# nRF-Serial-v12-Class-vrs.net
KiCad netlist of a schematic drawn in EAGLE
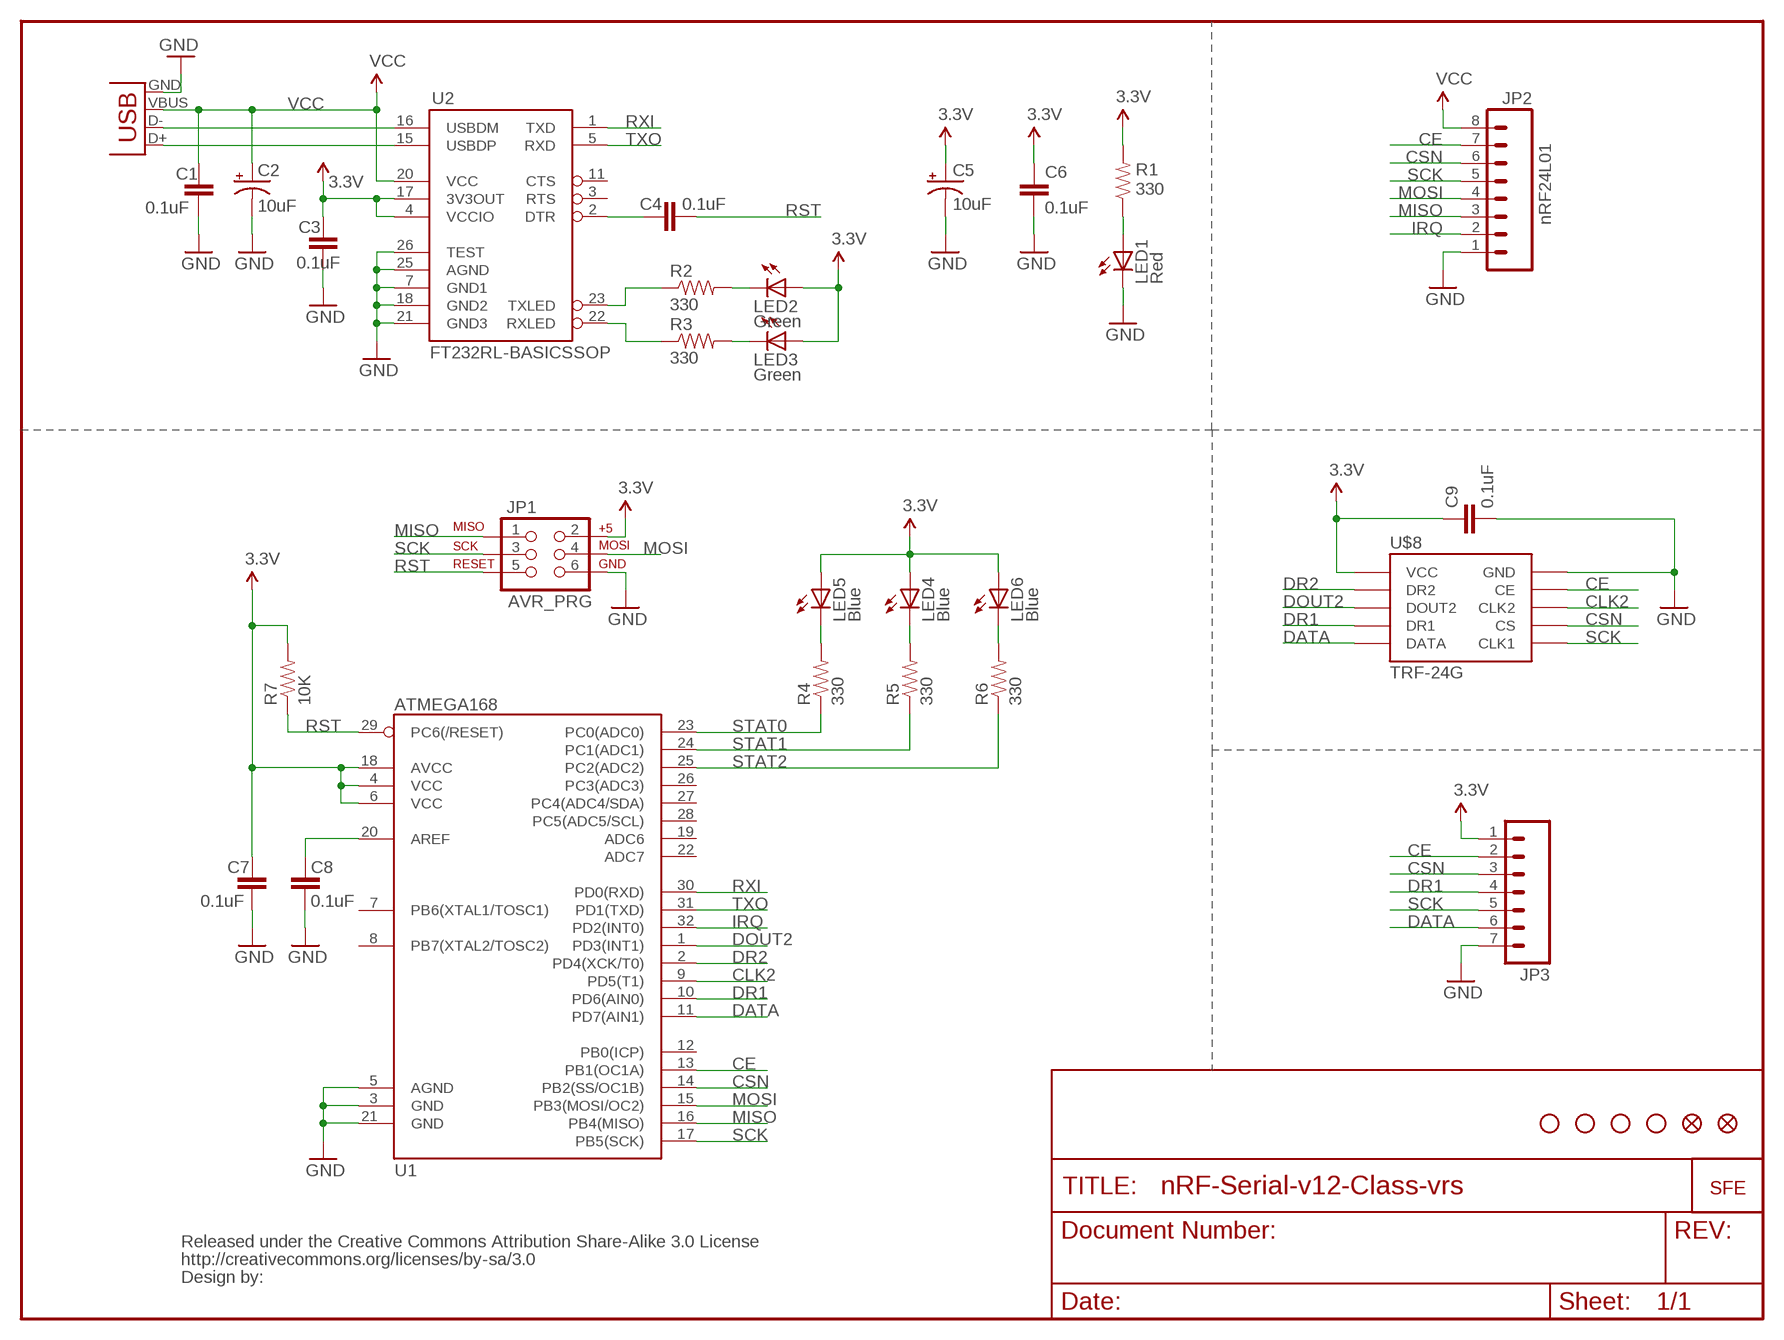
[diagram p0: schematic, sheet 1]

(export (version "E")
  (design (tool "Eeschema 10.0.6"))
  (components
    (comp (ref "C1")
      (value "0.1uF")
      (footprint "eagle-import:C0402")
      (libsource (lib "eagle-import") (part "CAP0402"))
    )
    (comp (ref "C2")
      (value "10uF")
      (footprint "eagle-import:EIA3216")
      (libsource (lib "eagle-import") (part "CAP_POL1206"))
    )
    (comp (ref "C3")
      (value "0.1uF")
      (footprint "eagle-import:C0402")
      (libsource (lib "eagle-import") (part "CAP0402"))
    )
    (comp (ref "C4")
      (value "0.1uF")
      (footprint "eagle-import:C0402")
      (libsource (lib "eagle-import") (part "CAP0402"))
    )
    (comp (ref "C5")
      (value "10uF")
      (footprint "eagle-import:EIA3216")
      (libsource (lib "eagle-import") (part "CAP_POL1206"))
    )
    (comp (ref "C6")
      (value "0.1uF")
      (footprint "eagle-import:C0402")
      (libsource (lib "eagle-import") (part "CAP0402"))
    )
    (comp (ref "C7")
      (value "0.1uF")
      (footprint "eagle-import:C0402")
      (libsource (lib "eagle-import") (part "CAP0402"))
    )
    (comp (ref "C8")
      (value "0.1uF")
      (footprint "eagle-import:C0402")
      (libsource (lib "eagle-import") (part "CAP0402"))
    )
    (comp (ref "C9")
      (value "0.1uF")
      (footprint "eagle-import:C0402")
      (libsource (lib "eagle-import") (part "CAP0402"))
    )
    (comp (ref "JP1")
      (value "AVR_PRG")
      (footprint "eagle-import:2X3")
      (libsource (lib "eagle-import") (part "AVR_SPI_PRG_6PTH"))
    )
    (comp (ref "JP2")
      (value "nRF24L01")
      (footprint "eagle-import:1X08")
      (libsource (lib "eagle-import") (part "M08"))
    )
    (comp (ref "JP3")
      (value "M07")
      (footprint "eagle-import:1X07")
      (libsource (lib "eagle-import") (part "M07"))
    )
    (comp (ref "LED1")
      (value "Red")
      (footprint "eagle-import:LED-0603")
      (libsource (lib "eagle-import") (part "LED0603"))
    )
    (comp (ref "LED2")
      (value "Green")
      (footprint "eagle-import:LED-0603")
      (libsource (lib "eagle-import") (part "LED0603"))
    )
    (comp (ref "LED3")
      (value "Green")
      (footprint "eagle-import:LED-0603")
      (libsource (lib "eagle-import") (part "LED0603"))
    )
    (comp (ref "LED4")
      (value "Blue")
      (footprint "eagle-import:LED-0603")
      (libsource (lib "eagle-import") (part "LED0603"))
    )
    (comp (ref "LED5")
      (value "Blue")
      (footprint "eagle-import:LED-0603")
      (libsource (lib "eagle-import") (part "LED0603"))
    )
    (comp (ref "LED6")
      (value "Blue")
      (footprint "eagle-import:LED-0603")
      (libsource (lib "eagle-import") (part "LED0603"))
    )
    (comp (ref "R1")
      (value "330")
      (footprint "eagle-import:C0402")
      (libsource (lib "eagle-import") (part "RESISTOR0402"))
    )
    (comp (ref "R2")
      (value "330")
      (footprint "eagle-import:C0402")
      (libsource (lib "eagle-import") (part "RESISTOR0402"))
    )
    (comp (ref "R3")
      (value "330")
      (footprint "eagle-import:C0402")
      (libsource (lib "eagle-import") (part "RESISTOR0402"))
    )
    (comp (ref "R4")
      (value "330")
      (footprint "eagle-import:C0402")
      (libsource (lib "eagle-import") (part "RESISTOR0402"))
    )
    (comp (ref "R5")
      (value "330")
      (footprint "eagle-import:C0402")
      (libsource (lib "eagle-import") (part "RESISTOR0402"))
    )
    (comp (ref "R6")
      (value "330")
      (footprint "eagle-import:C0402")
      (libsource (lib "eagle-import") (part "RESISTOR0402"))
    )
    (comp (ref "R7")
      (value "10K")
      (footprint "eagle-import:C0402")
      (libsource (lib "eagle-import") (part "RESISTOR0402"))
    )
    (comp (ref "U$1")
      (value "LOGO-SFENEW")
      (footprint "eagle-import:SFE-NEW-WEBLOGO")
      (libsource (lib "eagle-import") (part "LOGO-SFENEW"))
    )
    (comp (ref "U$2")
      (value "FIDUCIAL1X2")
      (footprint "eagle-import:FIDUCIAL-1X2")
      (libsource (lib "eagle-import") (part "FIDUCIAL1X2"))
    )
    (comp (ref "U$3")
      (value "FIDUCIAL1X2")
      (footprint "eagle-import:FIDUCIAL-1X2")
      (libsource (lib "eagle-import") (part "FIDUCIAL1X2"))
    )
    (comp (ref "U$4")
      (value "STAND-OFF")
      (footprint "eagle-import:STAND-OFF")
      (libsource (lib "eagle-import") (part "STAND-OFF"))
    )
    (comp (ref "U$5")
      (value "STAND-OFF")
      (footprint "eagle-import:STAND-OFF")
      (libsource (lib "eagle-import") (part "STAND-OFF"))
    )
    (comp (ref "U$6")
      (value "STAND-OFF")
      (footprint "eagle-import:STAND-OFF")
      (libsource (lib "eagle-import") (part "STAND-OFF"))
    )
    (comp (ref "U$7")
      (value "STAND-OFF")
      (footprint "eagle-import:STAND-OFF")
      (libsource (lib "eagle-import") (part "STAND-OFF"))
    )
    (comp (ref "U$8")
      (value "TRF-24G")
      (footprint "eagle-import:TRF-24G-SOCKET")
      (libsource (lib "eagle-import") (part "TRF-24G"))
    )
    (comp (ref "U$9")
      (value "CREATIVE_COMMONS")
      (footprint "eagle-import:CREATIVE_COMMONS")
      (libsource (lib "eagle-import") (part "CREATIVE_COMMONS"))
    )
    (comp (ref "U1")
      (value "ATMEGA168")
      (footprint "eagle-import:TQFP32-08")
      (libsource (lib "eagle-import") (part "ATMEGA168"))
    )
    (comp (ref "U2")
      (value "FT232RL-BASICSSOP")
      (footprint "eagle-import:SSOP28DB")
      (libsource (lib "eagle-import") (part "FT232RL-BASICSSOP"))
    )
    (comp (ref "X1")
      (value "USBSMD")
      (footprint "eagle-import:USB-MINIB")
      (libsource (lib "eagle-import") (part "USBSMD"))
    )
  )
  (nets
    (net (code "1") (name "/CE") (class "Default")
      (node (ref "JP2") (pin "7") (pinfunction "7_7") (pintype "passive"))
      (node (ref "JP3") (pin "2") (pinfunction "2_2") (pintype "passive"))
      (node (ref "U$8") (pin "P$9") (pinfunction "CE_P$9") (pintype "bidirectional"))
      (node (ref "U1") (pin "13") (pinfunction "PB1(OC1A)_13") (pintype "bidirectional"))
    )
    (net (code "2") (name "/CLK2") (class "Default")
      (node (ref "U$8") (pin "P$8") (pinfunction "CLK2_P$8") (pintype "bidirectional"))
      (node (ref "U1") (pin "9") (pinfunction "PD5(T1)_9") (pintype "bidirectional"))
    )
    (net (code "3") (name "/CSN") (class "Default")
      (node (ref "JP2") (pin "6") (pinfunction "6_6") (pintype "passive"))
      (node (ref "JP3") (pin "3") (pinfunction "3_3") (pintype "passive"))
      (node (ref "U$8") (pin "P$7") (pinfunction "CS_P$7") (pintype "bidirectional"))
      (node (ref "U1") (pin "14") (pinfunction "PB2(SS/OC1B)_14") (pintype "bidirectional"))
    )
    (net (code "4") (name "/DATA") (class "Default")
      (node (ref "JP3") (pin "6") (pinfunction "6_6") (pintype "passive"))
      (node (ref "U$8") (pin "P$5") (pinfunction "DATA_P$5") (pintype "bidirectional"))
      (node (ref "U1") (pin "11") (pinfunction "PD7(AIN1)_11") (pintype "bidirectional"))
    )
    (net (code "5") (name "/DOUT2") (class "Default")
      (node (ref "U$8") (pin "P$3") (pinfunction "DOUT2_P$3") (pintype "bidirectional"))
      (node (ref "U1") (pin "1") (pinfunction "PD3(INT1)_1") (pintype "bidirectional"))
    )
    (net (code "6") (name "/DR1") (class "Default")
      (node (ref "JP3") (pin "4") (pinfunction "4_4") (pintype "passive"))
      (node (ref "U$8") (pin "P$4") (pinfunction "DR1_P$4") (pintype "bidirectional"))
      (node (ref "U1") (pin "10") (pinfunction "PD6(AIN0)_10") (pintype "bidirectional"))
    )
    (net (code "7") (name "/DR2") (class "Default")
      (node (ref "U$8") (pin "P$2") (pinfunction "DR2_P$2") (pintype "bidirectional"))
      (node (ref "U1") (pin "2") (pinfunction "PD4(XCK/T0)_2") (pintype "bidirectional"))
    )
    (net (code "8") (name "/IRQ") (class "Default")
      (node (ref "JP2") (pin "2") (pinfunction "2_2") (pintype "passive"))
      (node (ref "U1") (pin "32") (pinfunction "PD2(INT0)_32") (pintype "bidirectional"))
    )
    (net (code "9") (name "/MISO") (class "Default")
      (node (ref "JP1") (pin "1") (pinfunction "1_1") (pintype "passive"))
      (node (ref "JP2") (pin "3") (pinfunction "3_3") (pintype "passive"))
      (node (ref "U1") (pin "16") (pinfunction "PB4(MISO)_16") (pintype "bidirectional"))
    )
    (net (code "10") (name "/MOSI") (class "Default")
      (node (ref "JP1") (pin "4") (pinfunction "4_4") (pintype "passive"))
      (node (ref "JP2") (pin "4") (pinfunction "4_4") (pintype "passive"))
      (node (ref "U1") (pin "15") (pinfunction "PB3(MOSI/OC2)_15") (pintype "bidirectional"))
    )
    (net (code "11") (name "/RST") (class "Default")
      (node (ref "C4") (pin "1") (pinfunction "1_1") (pintype "passive"))
      (node (ref "JP1") (pin "5") (pinfunction "5_5") (pintype "passive"))
      (node (ref "R7") (pin "1") (pinfunction "1_1") (pintype "passive"))
      (node (ref "U1") (pin "29") (pinfunction "PC6(/RESET)_29") (pintype "bidirectional"))
    )
    (net (code "12") (name "/RXI") (class "Default")
      (node (ref "U1") (pin "30") (pinfunction "PD0(RXD)_30") (pintype "bidirectional"))
      (node (ref "U2") (pin "1") (pinfunction "TXD_1") (pintype "output"))
    )
    (net (code "13") (name "/SCK") (class "Default")
      (node (ref "JP1") (pin "3") (pinfunction "3_3") (pintype "passive"))
      (node (ref "JP2") (pin "5") (pinfunction "5_5") (pintype "passive"))
      (node (ref "JP3") (pin "5") (pinfunction "5_5") (pintype "passive"))
      (node (ref "U$8") (pin "P$6") (pinfunction "CLK1_P$6") (pintype "bidirectional"))
      (node (ref "U1") (pin "17") (pinfunction "PB5(SCK)_17") (pintype "bidirectional"))
    )
    (net (code "14") (name "/STAT0") (class "Default")
      (node (ref "R4") (pin "1") (pinfunction "1_1") (pintype "passive"))
      (node (ref "U1") (pin "23") (pinfunction "PC0(ADC0)_23") (pintype "bidirectional"))
    )
    (net (code "15") (name "/STAT1") (class "Default")
      (node (ref "R5") (pin "1") (pinfunction "1_1") (pintype "passive"))
      (node (ref "U1") (pin "24") (pinfunction "PC1(ADC1)_24") (pintype "bidirectional"))
    )
    (net (code "16") (name "/STAT2") (class "Default")
      (node (ref "R6") (pin "1") (pinfunction "1_1") (pintype "passive"))
      (node (ref "U1") (pin "25") (pinfunction "PC2(ADC2)_25") (pintype "bidirectional"))
    )
    (net (code "17") (name "/TXO") (class "Default")
      (node (ref "U1") (pin "31") (pinfunction "PD1(TXD)_31") (pintype "bidirectional"))
      (node (ref "U2") (pin "5") (pinfunction "RXD_5") (pintype "input"))
    )
    (net (code "18") (name "3.3V") (class "Default")
      (node (ref "C3") (pin "1") (pinfunction "1_1") (pintype "passive"))
      (node (ref "C5") (pin "A") (pinfunction "+_A") (pintype "passive"))
      (node (ref "C6") (pin "1") (pinfunction "1_1") (pintype "passive"))
      (node (ref "C7") (pin "1") (pinfunction "1_1") (pintype "passive"))
      (node (ref "C9") (pin "1") (pinfunction "1_1") (pintype "passive"))
      (node (ref "JP1") (pin "2") (pinfunction "2_2") (pintype "passive"))
      (node (ref "JP3") (pin "1") (pinfunction "1_1") (pintype "passive"))
      (node (ref "LED2") (pin "A") (pinfunction "A_A") (pintype "passive"))
      (node (ref "LED3") (pin "A") (pinfunction "A_A") (pintype "passive"))
      (node (ref "LED4") (pin "A") (pinfunction "A_A") (pintype "passive"))
      (node (ref "LED5") (pin "A") (pinfunction "A_A") (pintype "passive"))
      (node (ref "LED6") (pin "A") (pinfunction "A_A") (pintype "passive"))
      (node (ref "R1") (pin "2") (pinfunction "2_2") (pintype "passive"))
      (node (ref "R7") (pin "2") (pinfunction "2_2") (pintype "passive"))
      (node (ref "U$8") (pin "P$1") (pinfunction "VCC_P$1") (pintype "bidirectional"))
      (node (ref "U1") (pin "18") (pinfunction "AVCC_18") (pintype "bidirectional"))
      (node (ref "U1") (pin "4") (pinfunction "VCC_4") (pintype "bidirectional"))
      (node (ref "U1") (pin "6") (pinfunction "VCC_6") (pintype "bidirectional"))
      (node (ref "U2") (pin "17") (pinfunction "3V3OUT_17") (pintype "output"))
      (node (ref "U2") (pin "4") (pinfunction "VCCIO_4") (pintype "power_in"))
    )
    (net (code "19") (name "GND") (class "Default")
      (node (ref "C1") (pin "2") (pinfunction "2_2") (pintype "passive"))
      (node (ref "C2") (pin "C") (pinfunction "-_C") (pintype "passive"))
      (node (ref "C3") (pin "2") (pinfunction "2_2") (pintype "passive"))
      (node (ref "C5") (pin "C") (pinfunction "-_C") (pintype "passive"))
      (node (ref "C6") (pin "2") (pinfunction "2_2") (pintype "passive"))
      (node (ref "C7") (pin "2") (pinfunction "2_2") (pintype "passive"))
      (node (ref "C8") (pin "1") (pinfunction "1_1") (pintype "passive"))
      (node (ref "C9") (pin "2") (pinfunction "2_2") (pintype "passive"))
      (node (ref "JP1") (pin "6") (pinfunction "6_6") (pintype "passive"))
      (node (ref "JP2") (pin "1") (pinfunction "1_1") (pintype "passive"))
      (node (ref "JP3") (pin "7") (pinfunction "7_7") (pintype "passive"))
      (node (ref "LED1") (pin "C") (pinfunction "C_C") (pintype "passive"))
      (node (ref "U$8") (pin "P$10") (pinfunction "GND_P$10") (pintype "bidirectional"))
      (node (ref "U1") (pin "21") (pinfunction "GND_21") (pintype "bidirectional"))
      (node (ref "U1") (pin "3") (pinfunction "GND_3") (pintype "bidirectional"))
      (node (ref "U1") (pin "5") (pinfunction "AGND_5") (pintype "bidirectional"))
      (node (ref "U2") (pin "18") (pinfunction "GND2_18") (pintype "power_in"))
      (node (ref "U2") (pin "21") (pinfunction "GND3_21") (pintype "power_in"))
      (node (ref "U2") (pin "25") (pinfunction "AGND_25") (pintype "power_in"))
      (node (ref "U2") (pin "26") (pinfunction "TEST_26") (pintype "input"))
      (node (ref "U2") (pin "7") (pinfunction "GND1_7") (pintype "power_in"))
      (node (ref "X1") (pin "GND") (pinfunction "GND_GND") (pintype "bidirectional"))
    )
    (net (code "20") (name "Net-(LED1-PadA)") (class "Default")
      (node (ref "LED1") (pin "A") (pinfunction "A_A") (pintype "passive"))
      (node (ref "R1") (pin "1") (pinfunction "1_1") (pintype "passive"))
    )
    (net (code "21") (name "Net-(LED2-PadC)") (class "Default")
      (node (ref "LED2") (pin "C") (pinfunction "C_C") (pintype "passive"))
      (node (ref "R2") (pin "2") (pinfunction "2_2") (pintype "passive"))
    )
    (net (code "22") (name "Net-(LED3-PadC)") (class "Default")
      (node (ref "LED3") (pin "C") (pinfunction "C_C") (pintype "passive"))
      (node (ref "R3") (pin "2") (pinfunction "2_2") (pintype "passive"))
    )
    (net (code "23") (name "Net-(LED4-PadC)") (class "Default")
      (node (ref "LED4") (pin "C") (pinfunction "C_C") (pintype "passive"))
      (node (ref "R5") (pin "2") (pinfunction "2_2") (pintype "passive"))
    )
    (net (code "24") (name "Net-(LED5-PadC)") (class "Default")
      (node (ref "LED5") (pin "C") (pinfunction "C_C") (pintype "passive"))
      (node (ref "R4") (pin "2") (pinfunction "2_2") (pintype "passive"))
    )
    (net (code "25") (name "Net-(LED6-PadC)") (class "Default")
      (node (ref "LED6") (pin "C") (pinfunction "C_C") (pintype "passive"))
      (node (ref "R6") (pin "2") (pinfunction "2_2") (pintype "passive"))
    )
    (net (code "26") (name "Net-(U1-AREF)") (class "Default")
      (node (ref "C8") (pin "2") (pinfunction "2_2") (pintype "passive"))
      (node (ref "U1") (pin "20") (pinfunction "AREF_20") (pintype "bidirectional"))
    )
    (net (code "27") (name "Net-(U2-DTR)") (class "Default")
      (node (ref "C4") (pin "2") (pinfunction "2_2") (pintype "passive"))
      (node (ref "U2") (pin "2") (pinfunction "DTR_2") (pintype "bidirectional"))
    )
    (net (code "28") (name "Net-(U2-RXLED)") (class "Default")
      (node (ref "R3") (pin "1") (pinfunction "1_1") (pintype "passive"))
      (node (ref "U2") (pin "22") (pinfunction "RXLED_22") (pintype "bidirectional"))
    )
    (net (code "29") (name "Net-(U2-TXLED)") (class "Default")
      (node (ref "R2") (pin "1") (pinfunction "1_1") (pintype "passive"))
      (node (ref "U2") (pin "23") (pinfunction "TXLED_23") (pintype "bidirectional"))
    )
    (net (code "30") (name "Net-(U2-USBDM)") (class "Default")
      (node (ref "U2") (pin "16") (pinfunction "USBDM_16") (pintype "bidirectional"))
      (node (ref "X1") (pin "D-") (pinfunction "D-_D-") (pintype "bidirectional"))
    )
    (net (code "31") (name "Net-(U2-USBDP)") (class "Default")
      (node (ref "U2") (pin "15") (pinfunction "USBDP_15") (pintype "bidirectional"))
      (node (ref "X1") (pin "D+") (pinfunction "D+_D+") (pintype "bidirectional"))
    )
    (net (code "32") (name "VCC") (class "Default")
      (node (ref "C1") (pin "1") (pinfunction "1_1") (pintype "passive"))
      (node (ref "C2") (pin "A") (pinfunction "+_A") (pintype "passive"))
      (node (ref "JP2") (pin "8") (pinfunction "8_8") (pintype "passive"))
      (node (ref "U2") (pin "20") (pinfunction "VCC_20") (pintype "power_in"))
      (node (ref "X1") (pin "VBUS") (pinfunction "VBUS_VBUS") (pintype "bidirectional"))
    )
    (net (code "33") (name "unconnected-(U1-ADC6-Pad19)") (class "Default")
      (node (ref "U1") (pin "19") (pinfunction "ADC6_19") (pintype "bidirectional"))
    )
    (net (code "34") (name "unconnected-(U1-ADC7-Pad22)") (class "Default")
      (node (ref "U1") (pin "22") (pinfunction "ADC7_22") (pintype "bidirectional"))
    )
    (net (code "35") (name "unconnected-(U1-PB0(ICP)-Pad12)") (class "Default")
      (node (ref "U1") (pin "12") (pinfunction "PB0(ICP)_12") (pintype "bidirectional"))
    )
    (net (code "36") (name "unconnected-(U1-PB6(XTAL1{slash}TOSC1)-Pad7)") (class "Default")
      (node (ref "U1") (pin "7") (pinfunction "PB6(XTAL1/TOSC1)_7") (pintype "bidirectional"))
    )
    (net (code "37") (name "unconnected-(U1-PB7(XTAL2{slash}TOSC2)-Pad8)") (class "Default")
      (node (ref "U1") (pin "8") (pinfunction "PB7(XTAL2/TOSC2)_8") (pintype "bidirectional"))
    )
    (net (code "38") (name "unconnected-(U1-PC3(ADC3)-Pad26)") (class "Default")
      (node (ref "U1") (pin "26") (pinfunction "PC3(ADC3)_26") (pintype "bidirectional"))
    )
    (net (code "39") (name "unconnected-(U1-PC4(ADC4{slash}SDA)-Pad27)") (class "Default")
      (node (ref "U1") (pin "27") (pinfunction "PC4(ADC4/SDA)_27") (pintype "bidirectional"))
    )
    (net (code "40") (name "unconnected-(U1-PC5(ADC5{slash}SCL)-Pad28)") (class "Default")
      (node (ref "U1") (pin "28") (pinfunction "PC5(ADC5/SCL)_28") (pintype "bidirectional"))
    )
    (net (code "41") (name "unconnected-(U2-CTS-Pad11)") (class "Default")
      (node (ref "U2") (pin "11") (pinfunction "CTS_11") (pintype "bidirectional"))
    )
    (net (code "42") (name "unconnected-(U2-RTS-Pad3)") (class "Default")
      (node (ref "U2") (pin "3") (pinfunction "RTS_3") (pintype "bidirectional"))
    )
  )
)
